# Discharge.net
KiCad netlist of a schematic drawn in Altium Designer
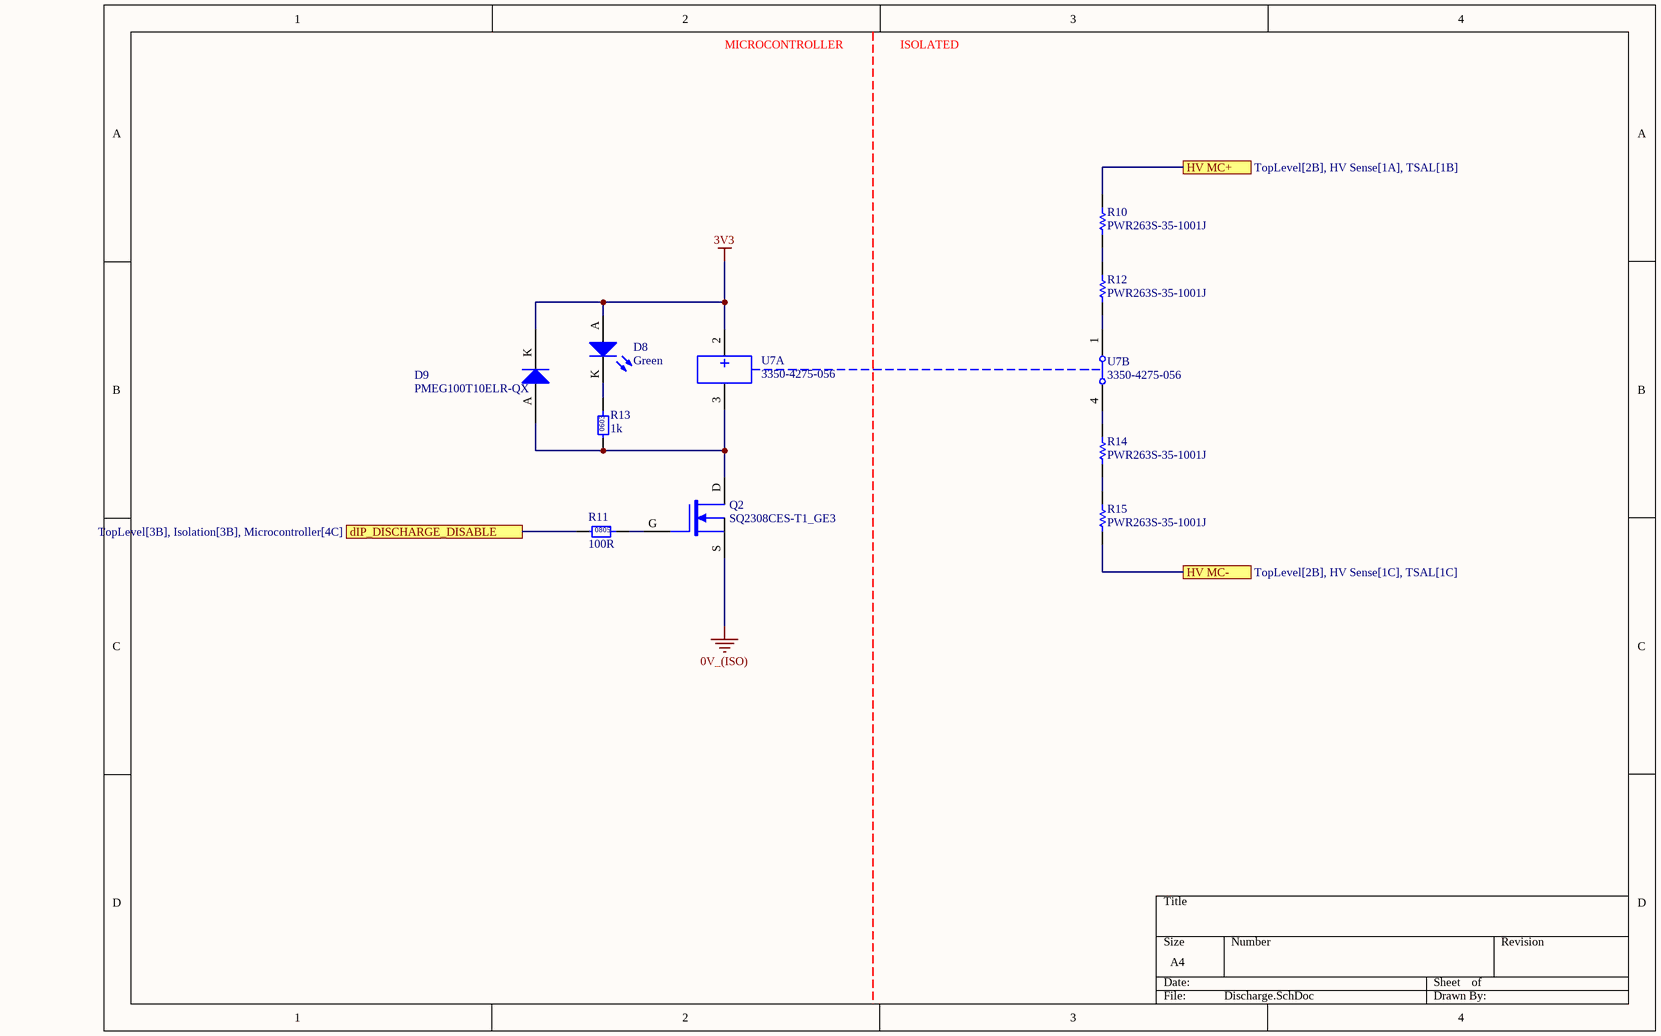
[diagram p0: Discharge.SchDoc]

(export (version "E")
  (design (tool "Eeschema 10.0.6"))
  (components
    (comp (ref "D8")
      (value "Green")
      (footprint "0805 LED")
      (description "Green LED Indication - Discrete 1.75V 0805 (2012 Metric)")
      (fields (field (name "PART NUMBER") "SML-210FTT86") (field (name "MANUFACTURER") "ROHM Semiconductor"))
      (libsource (lib "ts_standard_library") (part "LED"))
    )
    (comp (ref "D9")
      (value "PMEG100T10ELR-QX")
      (footprint "SODFL350X110-2N")
      (description "Diode 100 V 1A Surface Mount SOD-123W")
      (libsource (lib "Team Swinburne") (part "PMEG100T10ELR-QX"))
    )
    (comp (ref "Q2")
      (value "SQ2308CES-T1_GE3")
      (footprint "VSHY SOT-23-3")
      (description "MOSFET N-CH 60V 2.3A SOT23")
      (fields
        (field (name "MANUFACTURER") "Vishay Siliconix")
        (field (name "DIGIKEY PART NUMBER") "SQ2308CES-T1_GE3CT-ND")
        (field (name "PUBLISHER") "Altium Limited")
      )
      (libsource (lib "ts_standard_library") (part "MOSFET-N"))
    )
    (comp (ref "R10")
      (value "PWR263S-35-1001J")
      (footprint "B TO-263")
      (fields
        (field (name "MANUFACTURER") "Bournes Inc")
        (field (name "TOLERANCE") "0.05")
        (field (name "DIGIKEY PART NUMBER") "PWR263S-35-1001J-ND")
      )
      (libsource (lib "Team Swinburne") (part "Resistor"))
    )
    (comp (ref "R11")
      (value "100R")
      (footprint "0805")
      (fields
        (field (name "PART NUMBER") "RC0805FR07100RL")
        (field (name "MANUFACTURER") "YAGEO")
        (field (name "TOLERANCE") "0.01")
      )
      (libsource (lib "ts_standard_library") (part "Resistor 0805"))
    )
    (comp (ref "R12")
      (value "PWR263S-35-1001J")
      (footprint "B TO-263")
      (fields
        (field (name "MANUFACTURER") "Bournes Inc")
        (field (name "TOLERANCE") "0.05")
        (field (name "DIGIKEY PART NUMBER") "PWR263S-35-1001J-ND")
      )
      (libsource (lib "Team Swinburne") (part "Resistor"))
    )
    (comp (ref "R13")
      (value "1k")
      (footprint "0603")
      (fields
        (field (name "PART NUMBER") "RC0603FR-071KL")
        (field (name "MANUFACTURER") "YAGEO")
        (field (name "TOLERANCE") "0.01")
      )
      (libsource (lib "ts_standard_library") (part "Resistor 0603"))
    )
    (comp (ref "R14")
      (value "PWR263S-35-1001J")
      (footprint "B TO-263")
      (fields
        (field (name "MANUFACTURER") "Bournes Inc")
        (field (name "TOLERANCE") "0.05")
        (field (name "DIGIKEY PART NUMBER") "PWR263S-35-1001J-ND")
      )
      (libsource (lib "Team Swinburne") (part "Resistor"))
    )
    (comp (ref "R15")
      (value "PWR263S-35-1001J")
      (footprint "B TO-263")
      (fields
        (field (name "MANUFACTURER") "Bournes Inc")
        (field (name "TOLERANCE") "0.05")
        (field (name "DIGIKEY PART NUMBER") "PWR263S-35-1001J-ND")
      )
      (libsource (lib "Team Swinburne") (part "Resistor"))
    )
    (comp (ref "U7")
      (value "3350-4275-056")
      (footprint "CI SPST")
      (description "RELAY REED HV SPST 200W 3A 5V (NC)")
      (libsource (lib "Team Swinburne") (part "3350-4275-056"))
    )
  )
  (nets
    (net (code "1") (name "/HV MC+") (class "Default")
      (node (ref "R10") (pin "1") (pinfunction "1_1") (pintype "passive"))
    )
    (net (code "2") (name "/HV MC-") (class "Default")
      (node (ref "R15") (pin "2") (pinfunction "2_2") (pintype "passive"))
    )
    (net (code "3") (name "/dIP_DISCHARGE_DISABLE") (class "Default")
      (node (ref "R11") (pin "1") (pinfunction "1_1") (pintype "passive"))
    )
    (net (code "4") (name "0V_(ISO)") (class "Default")
      (node (ref "Q2") (pin "S") (pinfunction "S_S") (pintype "passive"))
    )
    (net (code "5") (name "3V3") (class "Default")
      (node (ref "D8") (pin "A") (pinfunction "A_A") (pintype "passive"))
      (node (ref "D9") (pin "K") (pintype "passive"))
      (node (ref "U7") (pin "2") (pinfunction "2_2") (pintype "passive"))
    )
    (net (code "6") (name "Net-(D8-PadK)") (class "Default")
      (node (ref "D8") (pin "K") (pinfunction "K_K") (pintype "passive"))
      (node (ref "R13") (pin "2") (pinfunction "2_2") (pintype "passive"))
    )
    (net (code "7") (name "Net-(D9-PadA)") (class "Default")
      (node (ref "D9") (pin "A") (pintype "passive"))
      (node (ref "Q2") (pin "D") (pinfunction "D_D") (pintype "passive"))
      (node (ref "R13") (pin "1") (pinfunction "1_1") (pintype "passive"))
      (node (ref "U7") (pin "3") (pinfunction "3_3") (pintype "passive"))
    )
    (net (code "8") (name "Net-(Q2-PadG)") (class "Default")
      (node (ref "Q2") (pin "G") (pinfunction "G_G") (pintype "passive"))
      (node (ref "R11") (pin "2") (pinfunction "2_2") (pintype "passive"))
    )
    (net (code "9") (name "Net-(R10-Pad2)") (class "Default")
      (node (ref "R10") (pin "2") (pinfunction "2_2") (pintype "passive"))
      (node (ref "R12") (pin "1") (pinfunction "1_1") (pintype "passive"))
    )
    (net (code "10") (name "Net-(R12-Pad2)") (class "Default")
      (node (ref "R12") (pin "2") (pinfunction "2_2") (pintype "passive"))
      (node (ref "U7") (pin "1") (pinfunction "1_1") (pintype "passive"))
    )
    (net (code "11") (name "Net-(R14-Pad1)") (class "Default")
      (node (ref "R14") (pin "1") (pinfunction "1_1") (pintype "passive"))
      (node (ref "U7") (pin "4") (pinfunction "4_4") (pintype "passive"))
    )
    (net (code "12") (name "Net-(R14-Pad2)") (class "Default")
      (node (ref "R14") (pin "2") (pinfunction "2_2") (pintype "passive"))
      (node (ref "R15") (pin "1") (pinfunction "1_1") (pintype "passive"))
    )
  )
)
